# wagband_schematic_v1_FINAL.net
KiCad netlist of a schematic drawn in EAGLE
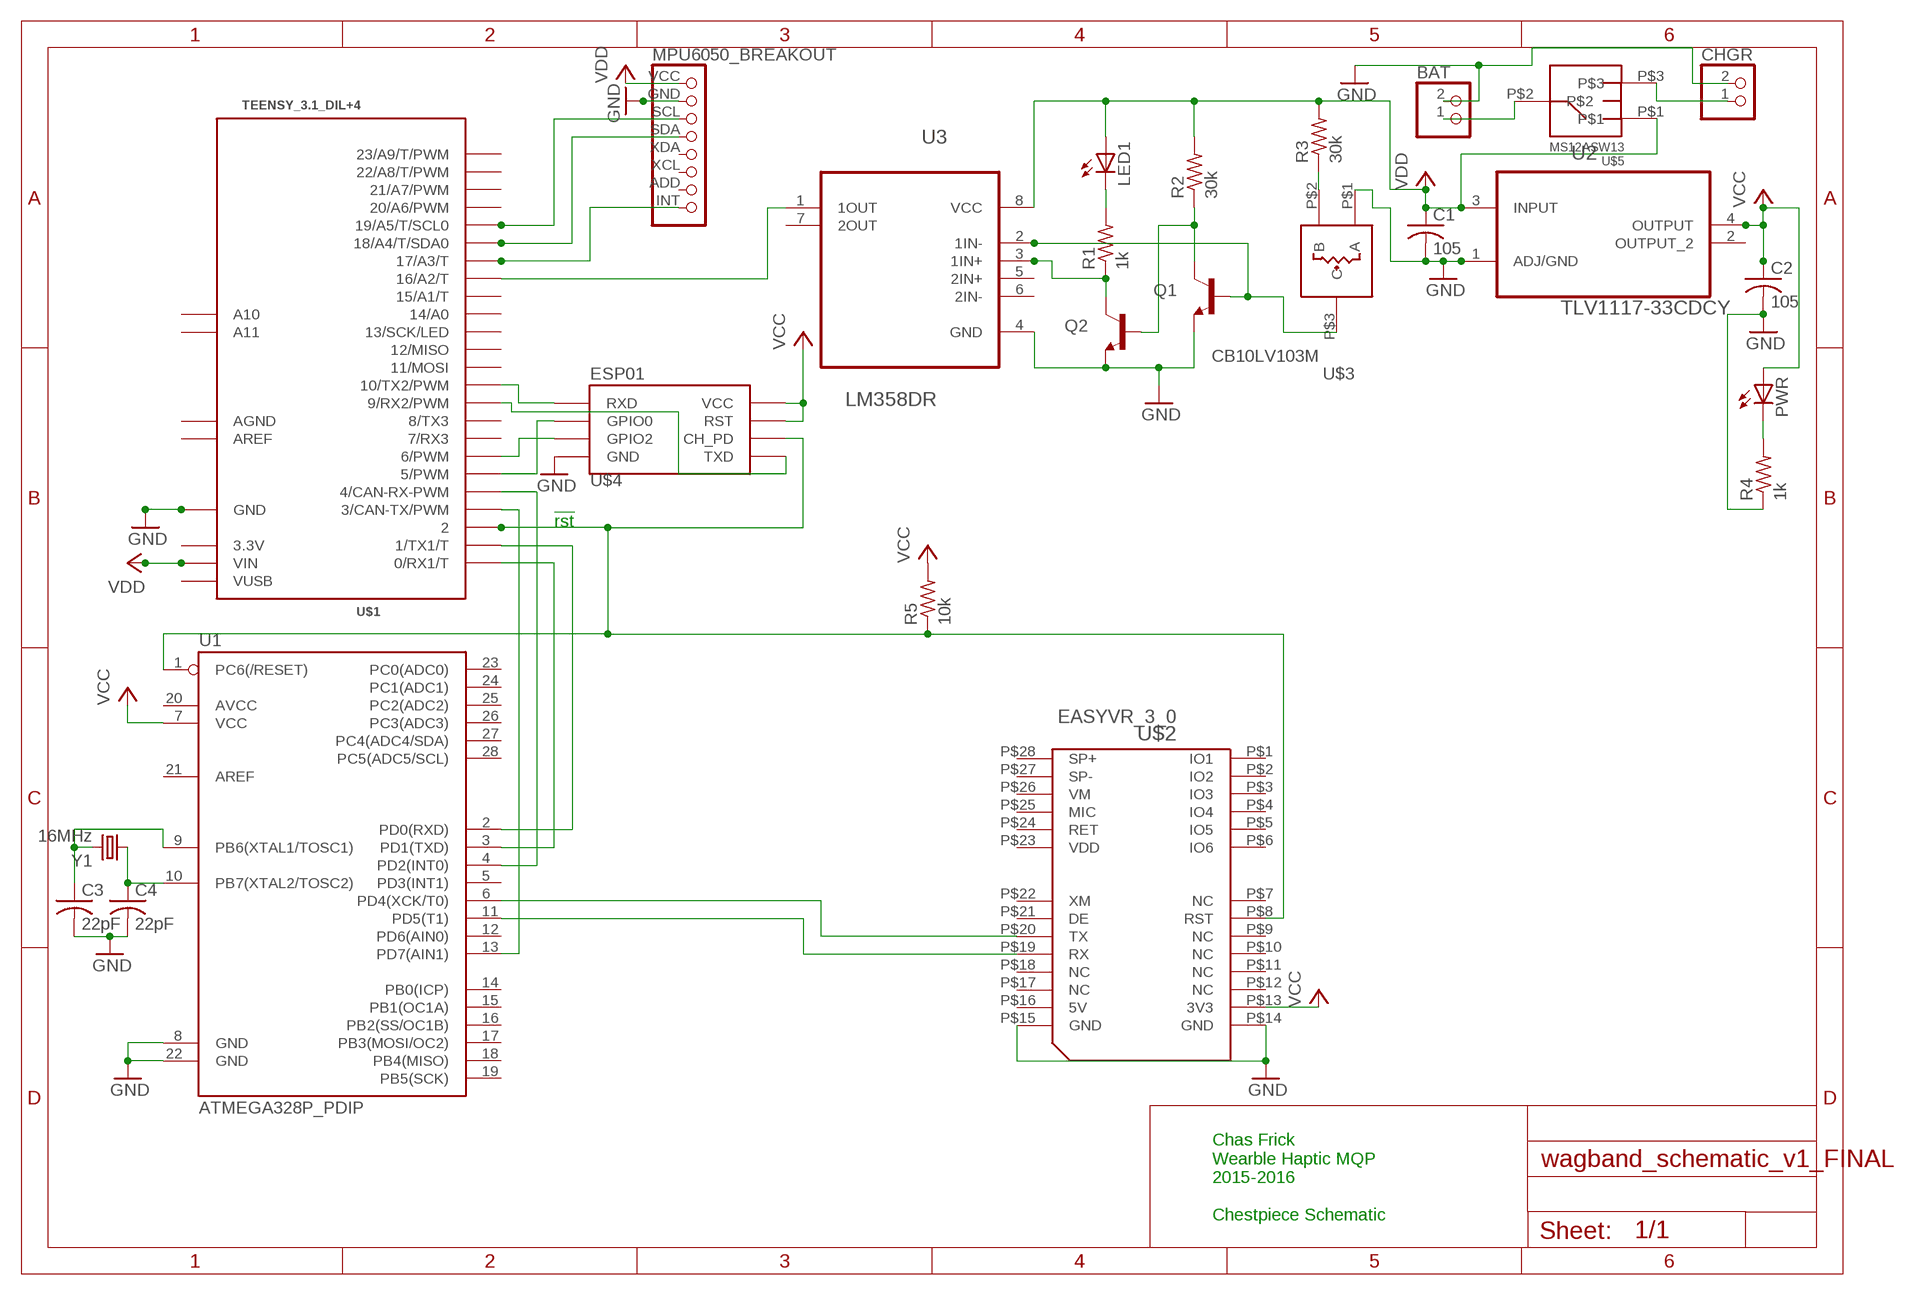
[diagram p0: schematic, sheet 1]

(export (version "E")
  (design (tool "Eeschema 10.0.6"))
  (components
    (comp (ref "BAT")
      (value "JST_2PIN-THM-RA")
      (footprint "eagle-import:JST-PH-2-THM-RA")
      (libsource (lib "eagle-import") (part "JST_2PIN-THM-RA"))
    )
    (comp (ref "C1")
      (value "105")
      (footprint "eagle-import:C0805K")
      (libsource (lib "eagle-import") (part "resistor_C-USC0805K"))
    )
    (comp (ref "C2")
      (value "105")
      (footprint "eagle-import:C0805K")
      (libsource (lib "eagle-import") (part "resistor_C-USC0805K"))
    )
    (comp (ref "C3")
      (value "22pF")
      (footprint "eagle-import:C1206K")
      (libsource (lib "eagle-import") (part "C-USC1206K"))
    )
    (comp (ref "C4")
      (value "22pF")
      (footprint "eagle-import:C1206K")
      (libsource (lib "eagle-import") (part "C-USC1206K"))
    )
    (comp (ref "CHGR")
      (value "JST_2PIN-THM-RA")
      (footprint "eagle-import:JST-PH-2-THM-RA")
      (libsource (lib "eagle-import") (part "JST_2PIN-THM-RA"))
    )
    (comp (ref "LED1")
      (value "LED5MM")
      (footprint "eagle-import:LED5MM")
      (libsource (lib "eagle-import") (part "LED5MM"))
    )
    (comp (ref "MPU6050_BREAKOUT")
      (value "MPU6050_BREAKOUT")
      (footprint "eagle-import:MPU6050")
      (libsource (lib "eagle-import") (part "MPU6050_BREAKOUT"))
    )
    (comp (ref "PWR")
      (value "LED5MM")
      (footprint "eagle-import:LED5MM")
      (libsource (lib "eagle-import") (part "LED5MM"))
    )
    (comp (ref "Q1")
      (value "TRANSISTOR_NPNMMBT3904")
      (footprint "eagle-import:SOT-23")
      (libsource (lib "eagle-import") (part "TRANSISTOR_NPNMMBT3904"))
    )
    (comp (ref "Q2")
      (value "TRANSISTOR_NPNMMBT3904")
      (footprint "eagle-import:SOT-23")
      (libsource (lib "eagle-import") (part "TRANSISTOR_NPNMMBT3904"))
    )
    (comp (ref "R1")
      (value "1k")
      (footprint "eagle-import:R1206")
      (libsource (lib "eagle-import") (part "R-US_R1206"))
    )
    (comp (ref "R2")
      (value "30k")
      (footprint "eagle-import:R1206")
      (libsource (lib "eagle-import") (part "R-US_R1206"))
    )
    (comp (ref "R3")
      (value "30k")
      (footprint "eagle-import:R1206")
      (libsource (lib "eagle-import") (part "R-US_R1206"))
    )
    (comp (ref "R4")
      (value "1k")
      (footprint "eagle-import:R1206")
      (libsource (lib "eagle-import") (part "R-US_R1206"))
    )
    (comp (ref "R5")
      (value "10k")
      (footprint "eagle-import:R1206")
      (libsource (lib "eagle-import") (part "R-US_R1206"))
    )
    (comp (ref "U$1")
      (value "TEENSY_3.1_DIL+4")
      (footprint "eagle-import:TEENSY3-DIL+4")
      (libsource (lib "eagle-import") (part "TEENSY_3.1_DIL+4"))
    )
    (comp (ref "U$2")
      (value "EASYVR_3_0")
      (footprint "eagle-import:EASYVR_3_0")
      (libsource (lib "eagle-import") (part "EASYVR_3_0"))
    )
    (comp (ref "U$3")
      (value "CB10LV103M")
      (footprint "eagle-import:CB10")
      (libsource (lib "eagle-import") (part "CB10LV103M"))
    )
    (comp (ref "U$4")
      (value "ESP01")
      (footprint "eagle-import:ESP01")
      (libsource (lib "eagle-import") (part "ESP01"))
    )
    (comp (ref "U$5")
      (value "MS12ASW13")
      (footprint "eagle-import:SPDT")
      (libsource (lib "eagle-import") (part "MS12ASW13"))
    )
    (comp (ref "U1")
      (value "ATMEGA328P_PDIP")
      (footprint "eagle-import:DIL28-3")
      (libsource (lib "eagle-import") (part "ATMEGA328P_PDIP"))
    )
    (comp (ref "U2")
      (value "TLV1117-33CDCY")
      (footprint "eagle-import:SOT230P700X180-4N")
      (libsource (lib "eagle-import") (part "TLV1117-33CDCY"))
    )
    (comp (ref "U3")
      (value "LM358DR")
      (footprint "eagle-import:SOIC127P600X175-8N")
      (libsource (lib "eagle-import") (part "LM358DR"))
    )
    (comp (ref "Y1")
      (value "16MHz")
      (footprint "eagle-import:HC49UP")
      (libsource (lib "eagle-import") (part "CRYSTALSMD"))
    )
  )
  (nets
    (net (code "1") (name "/3.3V") (class "Default")
      (node (ref "U$1") (pin "3.3V") (pinfunction "3.3V_3.3V") (pintype "power_in"))
    )
    (net (code "2") (name "/AGND") (class "Default")
      (node (ref "U$1") (pin "AGND") (pinfunction "AGND_AGND") (pintype "power_in"))
    )
    (net (code "3") (name "/AREF") (class "Default")
      (node (ref "U$1") (pin "AREF") (pinfunction "AREF_AREF") (pintype "power_in"))
    )
    (net (code "4") (name "/VUSB") (class "Default")
      (node (ref "U$1") (pin "VUSB") (pinfunction "VUSB_VUSB") (pintype "power_in"))
    )
    (net (code "5") (name "GND") (class "Default")
      (node (ref "BAT") (pin "2") (pinfunction "1_2") (pintype "passive"))
      (node (ref "C1") (pin "2") (pinfunction "2_2") (pintype "passive"))
      (node (ref "C2") (pin "2") (pinfunction "2_2") (pintype "passive"))
      (node (ref "C3") (pin "2") (pinfunction "2_2") (pintype "passive"))
      (node (ref "C4") (pin "2") (pinfunction "2_2") (pintype "passive"))
      (node (ref "CHGR") (pin "2") (pinfunction "1_2") (pintype "passive"))
      (node (ref "MPU6050_BREAKOUT") (pin "GND") (pinfunction "GND_GND") (pintype "passive"))
      (node (ref "Q1") (pin "2") (pinfunction "E_2") (pintype "passive"))
      (node (ref "Q2") (pin "2") (pinfunction "E_2") (pintype "passive"))
      (node (ref "R4") (pin "1") (pinfunction "1_1") (pintype "passive"))
      (node (ref "U$1") (pin "GND") (pinfunction "GND_GND") (pintype "power_in"))
      (node (ref "U$2") (pin "P$14") (pinfunction "GND_P$14") (pintype "power_in"))
      (node (ref "U$2") (pin "P$15") (pinfunction "GND_P$15") (pintype "power_in"))
      (node (ref "U$3") (pin "P$1") (pinfunction "A_P$1") (pintype "bidirectional"))
      (node (ref "U$4") (pin "GND") (pinfunction "GND_GND") (pintype "bidirectional"))
      (node (ref "U1") (pin "22") (pinfunction "GND_22") (pintype "bidirectional"))
      (node (ref "U1") (pin "8") (pinfunction "GND_8") (pintype "bidirectional"))
      (node (ref "U2") (pin "1") (pinfunction "ADJ/GND_1") (pintype "input"))
      (node (ref "U3") (pin "4") (pinfunction "GND_4") (pintype "passive"))
    )
    (net (code "6") (name "Net-(BAT-2)") (class "Default")
      (node (ref "BAT") (pin "1") (pinfunction "2_1") (pintype "passive"))
      (node (ref "U$5") (pin "P$2") (pinfunction "P$2_P$2") (pintype "bidirectional"))
    )
    (net (code "7") (name "Net-(CHGR-2)") (class "Default")
      (node (ref "CHGR") (pin "1") (pinfunction "2_1") (pintype "passive"))
      (node (ref "U$5") (pin "P$3") (pinfunction "P$3_P$3") (pintype "bidirectional"))
    )
    (net (code "8") (name "Net-(LED1-C)") (class "Default")
      (node (ref "LED1") (pin "K") (pinfunction "C_K") (pintype "passive"))
      (node (ref "R1") (pin "2") (pinfunction "2_2") (pintype "passive"))
    )
    (net (code "9") (name "Net-(PWR-C)") (class "Default")
      (node (ref "PWR") (pin "K") (pinfunction "C_K") (pintype "passive"))
      (node (ref "R4") (pin "2") (pinfunction "2_2") (pintype "passive"))
    )
    (net (code "10") (name "Net-(Q1-B)") (class "Default")
      (node (ref "Q1") (pin "1") (pinfunction "B_1") (pintype "passive"))
      (node (ref "U$3") (pin "P$3") (pinfunction "C_P$3") (pintype "bidirectional"))
      (node (ref "U3") (pin "2") (pinfunction "1IN-_2") (pintype "input"))
    )
    (net (code "11") (name "Net-(Q1-C)") (class "Default")
      (node (ref "Q1") (pin "3") (pinfunction "C_3") (pintype "passive"))
      (node (ref "Q2") (pin "1") (pinfunction "B_1") (pintype "passive"))
      (node (ref "R2") (pin "1") (pinfunction "1_1") (pintype "passive"))
    )
    (net (code "12") (name "Net-(Q2-C)") (class "Default")
      (node (ref "Q2") (pin "3") (pinfunction "C_3") (pintype "passive"))
      (node (ref "R1") (pin "1") (pinfunction "1_1") (pintype "passive"))
      (node (ref "U3") (pin "3") (pinfunction "1IN+_3") (pintype "input"))
    )
    (net (code "13") (name "Net-(U$1-0{slash}RX1{slash}T)") (class "Default")
      (node (ref "U$1") (pin "0") (pinfunction "0/RX1/T_0") (pintype "bidirectional"))
      (node (ref "U1") (pin "3") (pinfunction "PD1(TXD)_3") (pintype "bidirectional"))
    )
    (net (code "14") (name "Net-(U$1-1{slash}TX1{slash}T)") (class "Default")
      (node (ref "U$1") (pin "1") (pinfunction "1/TX1/T_1") (pintype "bidirectional"))
      (node (ref "U1") (pin "2") (pinfunction "PD0(RXD)_2") (pintype "bidirectional"))
    )
    (net (code "15") (name "Net-(U$1-3{slash}CAN-TX{slash}PWM)") (class "Default")
      (node (ref "U$1") (pin "3") (pinfunction "3/CAN-TX/PWM_3") (pintype "bidirectional"))
      (node (ref "U1") (pin "13") (pinfunction "PD7(AIN1)_13") (pintype "bidirectional"))
    )
    (net (code "16") (name "Net-(U$1-4{slash}CAN-RX-PWM)") (class "Default")
      (node (ref "U$1") (pin "4") (pinfunction "4/CAN-RX-PWM_4") (pintype "bidirectional"))
      (node (ref "U1") (pin "4") (pinfunction "PD2(INT0)_4") (pintype "bidirectional"))
    )
    (net (code "17") (name "Net-(U$1-5{slash}PWM)") (class "Default")
      (node (ref "U$1") (pin "5") (pinfunction "5/PWM_5") (pintype "bidirectional"))
      (node (ref "U$4") (pin "GPIO0") (pinfunction "GPIO0_GPIO0") (pintype "bidirectional"))
    )
    (net (code "18") (name "Net-(U$1-6{slash}PWM)") (class "Default")
      (node (ref "U$1") (pin "6") (pinfunction "6/PWM_6") (pintype "bidirectional"))
      (node (ref "U$4") (pin "GPIO2") (pinfunction "GPIO2_GPIO2") (pintype "bidirectional"))
    )
    (net (code "19") (name "Net-(U$1-9{slash}RX2{slash}PWM)") (class "Default")
      (node (ref "U$1") (pin "9") (pinfunction "9/RX2/PWM_9") (pintype "bidirectional"))
      (node (ref "U$4") (pin "TX") (pinfunction "TXD_TX") (pintype "bidirectional"))
    )
    (net (code "20") (name "Net-(U$1-10{slash}TX2{slash}PWM)") (class "Default")
      (node (ref "U$1") (pin "10") (pinfunction "10/TX2/PWM_10") (pintype "bidirectional"))
      (node (ref "U$4") (pin "RX") (pinfunction "RXD_RX") (pintype "bidirectional"))
    )
    (net (code "21") (name "Net-(U$1-16{slash}A2{slash}T)") (class "Default")
      (node (ref "U$1") (pin "16/A2") (pinfunction "16/A2/T_16/A2") (pintype "bidirectional"))
      (node (ref "U3") (pin "1") (pinfunction "1OUT_1") (pintype "output"))
    )
    (net (code "22") (name "Net-(U$1-17{slash}A3{slash}T)") (class "Default")
      (node (ref "MPU6050_BREAKOUT") (pin "INT") (pinfunction "INT_INT") (pintype "passive"))
      (node (ref "U$1") (pin "17/A3") (pinfunction "17/A3/T_17/A3") (pintype "bidirectional"))
    )
    (net (code "23") (name "Net-(U$1-18{slash}A4{slash}T{slash}SDA0)") (class "Default")
      (node (ref "MPU6050_BREAKOUT") (pin "SDA") (pinfunction "SDA_SDA") (pintype "passive"))
      (node (ref "U$1") (pin "18/A4") (pinfunction "18/A4/T/SDA0_18/A4") (pintype "bidirectional"))
    )
    (net (code "24") (name "Net-(U$1-19{slash}A5{slash}T{slash}SCL0)") (class "Default")
      (node (ref "MPU6050_BREAKOUT") (pin "SCL") (pinfunction "SCL_SCL") (pintype "passive"))
      (node (ref "U$1") (pin "19/A5") (pinfunction "19/A5/T/SCL0_19/A5") (pintype "bidirectional"))
    )
    (net (code "25") (name "Net-(U$2-RST)") (class "Default")
      (node (ref "R5") (pin "1") (pinfunction "1_1") (pintype "passive"))
      (node (ref "U$1") (pin "2") (pinfunction "2_2") (pintype "bidirectional"))
      (node (ref "U$2") (pin "P$8") (pinfunction "RST_P$8") (pintype "input"))
      (node (ref "U$4") (pin "CH_PD") (pinfunction "CH_PD_CH_PD") (pintype "bidirectional"))
      (node (ref "U1") (pin "1") (pinfunction "PC6(/RESET)_1") (pintype "bidirectional"))
    )
    (net (code "26") (name "Net-(U$2-RX)") (class "Default")
      (node (ref "U$2") (pin "P$19") (pinfunction "RX_P$19") (pintype "input"))
      (node (ref "U1") (pin "11") (pinfunction "PD5(T1)_11") (pintype "bidirectional"))
    )
    (net (code "27") (name "Net-(U$2-TX)") (class "Default")
      (node (ref "U$2") (pin "P$20") (pinfunction "TX_P$20") (pintype "output"))
      (node (ref "U1") (pin "6") (pinfunction "PD4(XCK/T0)_6") (pintype "bidirectional"))
    )
    (net (code "28") (name "Net-(U$3-B)") (class "Default")
      (node (ref "R3") (pin "1") (pinfunction "1_1") (pintype "passive"))
      (node (ref "U$3") (pin "P$2") (pinfunction "B_P$2") (pintype "bidirectional"))
    )
    (net (code "29") (name "Net-(U1-PB6(XTAL1{slash}TOSC1))") (class "Default")
      (node (ref "C3") (pin "1") (pinfunction "1_1") (pintype "passive"))
      (node (ref "U1") (pin "9") (pinfunction "PB6(XTAL1/TOSC1)_9") (pintype "bidirectional"))
      (node (ref "Y1") (pin "2") (pinfunction "2_2") (pintype "passive"))
    )
    (net (code "30") (name "Net-(U1-PB7(XTAL2{slash}TOSC2))") (class "Default")
      (node (ref "C4") (pin "1") (pinfunction "1_1") (pintype "passive"))
      (node (ref "U1") (pin "10") (pinfunction "PB7(XTAL2/TOSC2)_10") (pintype "bidirectional"))
      (node (ref "Y1") (pin "1") (pinfunction "1_1") (pintype "passive"))
    )
    (net (code "31") (name "VCC") (class "Default")
      (node (ref "C1") (pin "1") (pinfunction "1_1") (pintype "passive"))
      (node (ref "C2") (pin "1") (pinfunction "1_1") (pintype "passive"))
      (node (ref "LED1") (pin "A") (pinfunction "A_A") (pintype "passive"))
      (node (ref "MPU6050_BREAKOUT") (pin "VCC") (pinfunction "VCC_VCC") (pintype "passive"))
      (node (ref "PWR") (pin "A") (pinfunction "A_A") (pintype "passive"))
      (node (ref "R2") (pin "2") (pinfunction "2_2") (pintype "passive"))
      (node (ref "R3") (pin "2") (pinfunction "2_2") (pintype "passive"))
      (node (ref "R5") (pin "2") (pinfunction "2_2") (pintype "passive"))
      (node (ref "U$1") (pin "VIN") (pinfunction "VIN_VIN") (pintype "power_in"))
      (node (ref "U$2") (pin "P$13") (pinfunction "3V3_P$13") (pintype "power_in"))
      (node (ref "U$4") (pin "RST") (pinfunction "RST_RST") (pintype "bidirectional"))
      (node (ref "U$4") (pin "VCC") (pinfunction "VCC_VCC") (pintype "bidirectional"))
      (node (ref "U$5") (pin "P$1") (pinfunction "P$1_P$1") (pintype "bidirectional"))
      (node (ref "U1") (pin "7") (pinfunction "VCC_7") (pintype "bidirectional"))
      (node (ref "U2") (pin "3") (pinfunction "INPUT_3") (pintype "input"))
      (node (ref "U2") (pin "4") (pinfunction "OUTPUT_4") (pintype "output"))
      (node (ref "U3") (pin "8") (pinfunction "VCC_8") (pintype "power_in"))
    )
    (net (code "32") (name "unconnected-(MPU6050_BREAKOUT-PadADD)") (class "Default")
      (node (ref "MPU6050_BREAKOUT") (pin "ADD") (pinfunction "ADD_ADD") (pintype "passive"))
    )
    (net (code "33") (name "unconnected-(MPU6050_BREAKOUT-PadXCL)") (class "Default")
      (node (ref "MPU6050_BREAKOUT") (pin "XCL") (pinfunction "XCL_XCL") (pintype "passive"))
    )
    (net (code "34") (name "unconnected-(MPU6050_BREAKOUT-PadXDA)") (class "Default")
      (node (ref "MPU6050_BREAKOUT") (pin "XDA") (pinfunction "XDA_XDA") (pintype "passive"))
    )
    (net (code "35") (name "unconnected-(U$1-7{slash}RX3-Pad7)") (class "Default")
      (node (ref "U$1") (pin "7") (pinfunction "7/RX3_7") (pintype "bidirectional"))
    )
    (net (code "36") (name "unconnected-(U$1-8{slash}TX3-Pad8)") (class "Default")
      (node (ref "U$1") (pin "8") (pinfunction "8/TX3_8") (pintype "bidirectional"))
    )
    (net (code "37") (name "unconnected-(U$1-11{slash}MOSI-Pad11)") (class "Default")
      (node (ref "U$1") (pin "11") (pinfunction "11/MOSI_11") (pintype "bidirectional"))
    )
    (net (code "38") (name "unconnected-(U$1-12{slash}MISO-Pad12)") (class "Default")
      (node (ref "U$1") (pin "12") (pinfunction "12/MISO_12") (pintype "bidirectional"))
    )
    (net (code "39") (name "unconnected-(U$1-13{slash}SCK{slash}LED-Pad13)") (class "Default")
      (node (ref "U$1") (pin "13") (pinfunction "13/SCK/LED_13") (pintype "bidirectional"))
    )
    (net (code "40") (name "unconnected-(U$1-15{slash}A1{slash}T-Pad15{slash}A1)") (class "Default")
      (node (ref "U$1") (pin "15/A1") (pinfunction "15/A1/T_15/A1") (pintype "bidirectional"))
    )
    (net (code "41") (name "unconnected-(U$1-20{slash}A6{slash}PWM-Pad20{slash}A6)") (class "Default")
      (node (ref "U$1") (pin "20/A6") (pinfunction "20/A6/PWM_20/A6") (pintype "bidirectional"))
    )
    (net (code "42") (name "unconnected-(U$1-21{slash}A7{slash}PWM-Pad21{slash}A7)") (class "Default")
      (node (ref "U$1") (pin "21/A7") (pinfunction "21/A7/PWM_21/A7") (pintype "bidirectional"))
    )
    (net (code "43") (name "unconnected-(U$1-22{slash}A8{slash}T{slash}PWM-Pad22{slash}A8)") (class "Default")
      (node (ref "U$1") (pin "22/A8") (pinfunction "22/A8/T/PWM_22/A8") (pintype "bidirectional"))
    )
    (net (code "44") (name "unconnected-(U$1-23{slash}A9{slash}T{slash}PWM-Pad23{slash}A9)") (class "Default")
      (node (ref "U$1") (pin "23/A9") (pinfunction "23/A9/T/PWM_23/A9") (pintype "bidirectional"))
    )
    (net (code "45") (name "unconnected-(U$1-Pad14{slash}A0)") (class "Default")
      (node (ref "U$1") (pin "14/A0") (pinfunction "14/A0_14/A0") (pintype "bidirectional"))
    )
    (net (code "46") (name "unconnected-(U$1-PadA10)") (class "Default")
      (node (ref "U$1") (pin "A10") (pinfunction "A10_A10") (pintype "bidirectional"))
    )
    (net (code "47") (name "unconnected-(U$1-PadA11)") (class "Default")
      (node (ref "U$1") (pin "A11") (pinfunction "A11_A11") (pintype "bidirectional"))
    )
    (net (code "48") (name "unconnected-(U$2-5V-PadP$16)") (class "Default")
      (node (ref "U$2") (pin "P$16") (pinfunction "5V_P$16") (pintype "power_in"))
    )
    (net (code "49") (name "unconnected-(U$2-DE-PadP$21)") (class "Default")
      (node (ref "U$2") (pin "P$21") (pinfunction "DE_P$21") (pintype "bidirectional"))
    )
    (net (code "50") (name "unconnected-(U$2-IO1-PadP$1)") (class "Default")
      (node (ref "U$2") (pin "P$1") (pinfunction "IO1_P$1") (pintype "bidirectional"))
    )
    (net (code "51") (name "unconnected-(U$2-IO2-PadP$2)") (class "Default")
      (node (ref "U$2") (pin "P$2") (pinfunction "IO2_P$2") (pintype "bidirectional"))
    )
    (net (code "52") (name "unconnected-(U$2-IO3-PadP$3)") (class "Default")
      (node (ref "U$2") (pin "P$3") (pinfunction "IO3_P$3") (pintype "bidirectional"))
    )
    (net (code "53") (name "unconnected-(U$2-IO4-PadP$4)") (class "Default")
      (node (ref "U$2") (pin "P$4") (pinfunction "IO4_P$4") (pintype "bidirectional"))
    )
    (net (code "54") (name "unconnected-(U$2-IO5-PadP$5)") (class "Default")
      (node (ref "U$2") (pin "P$5") (pinfunction "IO5_P$5") (pintype "bidirectional"))
    )
    (net (code "55") (name "unconnected-(U$2-IO6-PadP$6)") (class "Default")
      (node (ref "U$2") (pin "P$6") (pinfunction "IO6_P$6") (pintype "bidirectional"))
    )
    (net (code "56") (name "unconnected-(U$2-MIC-PadP$25)") (class "Default")
      (node (ref "U$2") (pin "P$25") (pinfunction "MIC_P$25") (pintype "bidirectional"))
    )
    (net (code "57") (name "unconnected-(U$2-NC-PadP$7)") (class "Default")
      (node (ref "U$2") (pin "P$7") (pinfunction "NC_P$7") (pintype "no_connect"))
    )
    (net (code "58") (name "unconnected-(U$2-NC-PadP$9)") (class "Default")
      (node (ref "U$2") (pin "P$9") (pinfunction "NC_P$9") (pintype "no_connect"))
    )
    (net (code "59") (name "unconnected-(U$2-NC-PadP$10)") (class "Default")
      (node (ref "U$2") (pin "P$10") (pinfunction "NC_P$10") (pintype "no_connect"))
    )
    (net (code "60") (name "unconnected-(U$2-NC-PadP$11)") (class "Default")
      (node (ref "U$2") (pin "P$11") (pinfunction "NC_P$11") (pintype "no_connect"))
    )
    (net (code "61") (name "unconnected-(U$2-NC-PadP$12)") (class "Default")
      (node (ref "U$2") (pin "P$12") (pinfunction "NC_P$12") (pintype "no_connect"))
    )
    (net (code "62") (name "unconnected-(U$2-NC-PadP$17)") (class "Default")
      (node (ref "U$2") (pin "P$17") (pinfunction "NC_P$17") (pintype "no_connect"))
    )
    (net (code "63") (name "unconnected-(U$2-NC-PadP$18)") (class "Default")
      (node (ref "U$2") (pin "P$18") (pinfunction "NC_P$18") (pintype "no_connect"))
    )
    (net (code "64") (name "unconnected-(U$2-RET-PadP$24)") (class "Default")
      (node (ref "U$2") (pin "P$24") (pinfunction "RET_P$24") (pintype "bidirectional"))
    )
    (net (code "65") (name "unconnected-(U$2-SP+-PadP$28)") (class "Default")
      (node (ref "U$2") (pin "P$28") (pinfunction "SP+_P$28") (pintype "bidirectional"))
    )
    (net (code "66") (name "unconnected-(U$2-SP--PadP$27)") (class "Default")
      (node (ref "U$2") (pin "P$27") (pinfunction "SP-_P$27") (pintype "bidirectional"))
    )
    (net (code "67") (name "unconnected-(U$2-VDD-PadP$23)") (class "Default")
      (node (ref "U$2") (pin "P$23") (pinfunction "VDD_P$23") (pintype "power_in"))
    )
    (net (code "68") (name "unconnected-(U$2-VM-PadP$26)") (class "Default")
      (node (ref "U$2") (pin "P$26") (pinfunction "VM_P$26") (pintype "bidirectional"))
    )
    (net (code "69") (name "unconnected-(U$2-XM-PadP$22)") (class "Default")
      (node (ref "U$2") (pin "P$22") (pinfunction "XM_P$22") (pintype "bidirectional"))
    )
    (net (code "70") (name "unconnected-(U1-AREF-Pad21)") (class "Default")
      (node (ref "U1") (pin "21") (pinfunction "AREF_21") (pintype "bidirectional"))
    )
    (net (code "71") (name "unconnected-(U1-AVCC-Pad20)") (class "Default")
      (node (ref "U1") (pin "20") (pinfunction "AVCC_20") (pintype "bidirectional"))
    )
    (net (code "72") (name "unconnected-(U1-PB0(ICP)-Pad14)") (class "Default")
      (node (ref "U1") (pin "14") (pinfunction "PB0(ICP)_14") (pintype "bidirectional"))
    )
    (net (code "73") (name "unconnected-(U1-PB1(OC1A)-Pad15)") (class "Default")
      (node (ref "U1") (pin "15") (pinfunction "PB1(OC1A)_15") (pintype "bidirectional"))
    )
    (net (code "74") (name "unconnected-(U1-PB2(SS{slash}OC1B)-Pad16)") (class "Default")
      (node (ref "U1") (pin "16") (pinfunction "PB2(SS/OC1B)_16") (pintype "bidirectional"))
    )
    (net (code "75") (name "unconnected-(U1-PB3(MOSI{slash}OC2)-Pad17)") (class "Default")
      (node (ref "U1") (pin "17") (pinfunction "PB3(MOSI/OC2)_17") (pintype "bidirectional"))
    )
    (net (code "76") (name "unconnected-(U1-PB4(MISO)-Pad18)") (class "Default")
      (node (ref "U1") (pin "18") (pinfunction "PB4(MISO)_18") (pintype "bidirectional"))
    )
    (net (code "77") (name "unconnected-(U1-PB5(SCK)-Pad19)") (class "Default")
      (node (ref "U1") (pin "19") (pinfunction "PB5(SCK)_19") (pintype "bidirectional"))
    )
    (net (code "78") (name "unconnected-(U1-PC0(ADC0)-Pad23)") (class "Default")
      (node (ref "U1") (pin "23") (pinfunction "PC0(ADC0)_23") (pintype "bidirectional"))
    )
    (net (code "79") (name "unconnected-(U1-PC1(ADC1)-Pad24)") (class "Default")
      (node (ref "U1") (pin "24") (pinfunction "PC1(ADC1)_24") (pintype "bidirectional"))
    )
    (net (code "80") (name "unconnected-(U1-PC2(ADC2)-Pad25)") (class "Default")
      (node (ref "U1") (pin "25") (pinfunction "PC2(ADC2)_25") (pintype "bidirectional"))
    )
    (net (code "81") (name "unconnected-(U1-PC3(ADC3)-Pad26)") (class "Default")
      (node (ref "U1") (pin "26") (pinfunction "PC3(ADC3)_26") (pintype "bidirectional"))
    )
    (net (code "82") (name "unconnected-(U1-PC4(ADC4{slash}SDA)-Pad27)") (class "Default")
      (node (ref "U1") (pin "27") (pinfunction "PC4(ADC4/SDA)_27") (pintype "bidirectional"))
    )
    (net (code "83") (name "unconnected-(U1-PC5(ADC5{slash}SCL)-Pad28)") (class "Default")
      (node (ref "U1") (pin "28") (pinfunction "PC5(ADC5/SCL)_28") (pintype "bidirectional"))
    )
    (net (code "84") (name "unconnected-(U1-PD3(INT1)-Pad5)") (class "Default")
      (node (ref "U1") (pin "5") (pinfunction "PD3(INT1)_5") (pintype "bidirectional"))
    )
    (net (code "85") (name "unconnected-(U1-PD6(AIN0)-Pad12)") (class "Default")
      (node (ref "U1") (pin "12") (pinfunction "PD6(AIN0)_12") (pintype "bidirectional"))
    )
    (net (code "86") (name "unconnected-(U2-OUTPUT_2-Pad2)") (class "Default")
      (node (ref "U2") (pin "2") (pinfunction "OUTPUT_2_2") (pintype "output"))
    )
    (net (code "87") (name "unconnected-(U3-2IN+-Pad5)") (class "Default")
      (node (ref "U3") (pin "5") (pinfunction "2IN+_5") (pintype "input"))
    )
    (net (code "88") (name "unconnected-(U3-2IN--Pad6)") (class "Default")
      (node (ref "U3") (pin "6") (pinfunction "2IN-_6") (pintype "input"))
    )
    (net (code "89") (name "unconnected-(U3-2OUT-Pad7)") (class "Default")
      (node (ref "U3") (pin "7") (pinfunction "2OUT_7") (pintype "output"))
    )
  )
)
